# -_-.net
KiCad netlist of a schematic drawn in Altium Designer
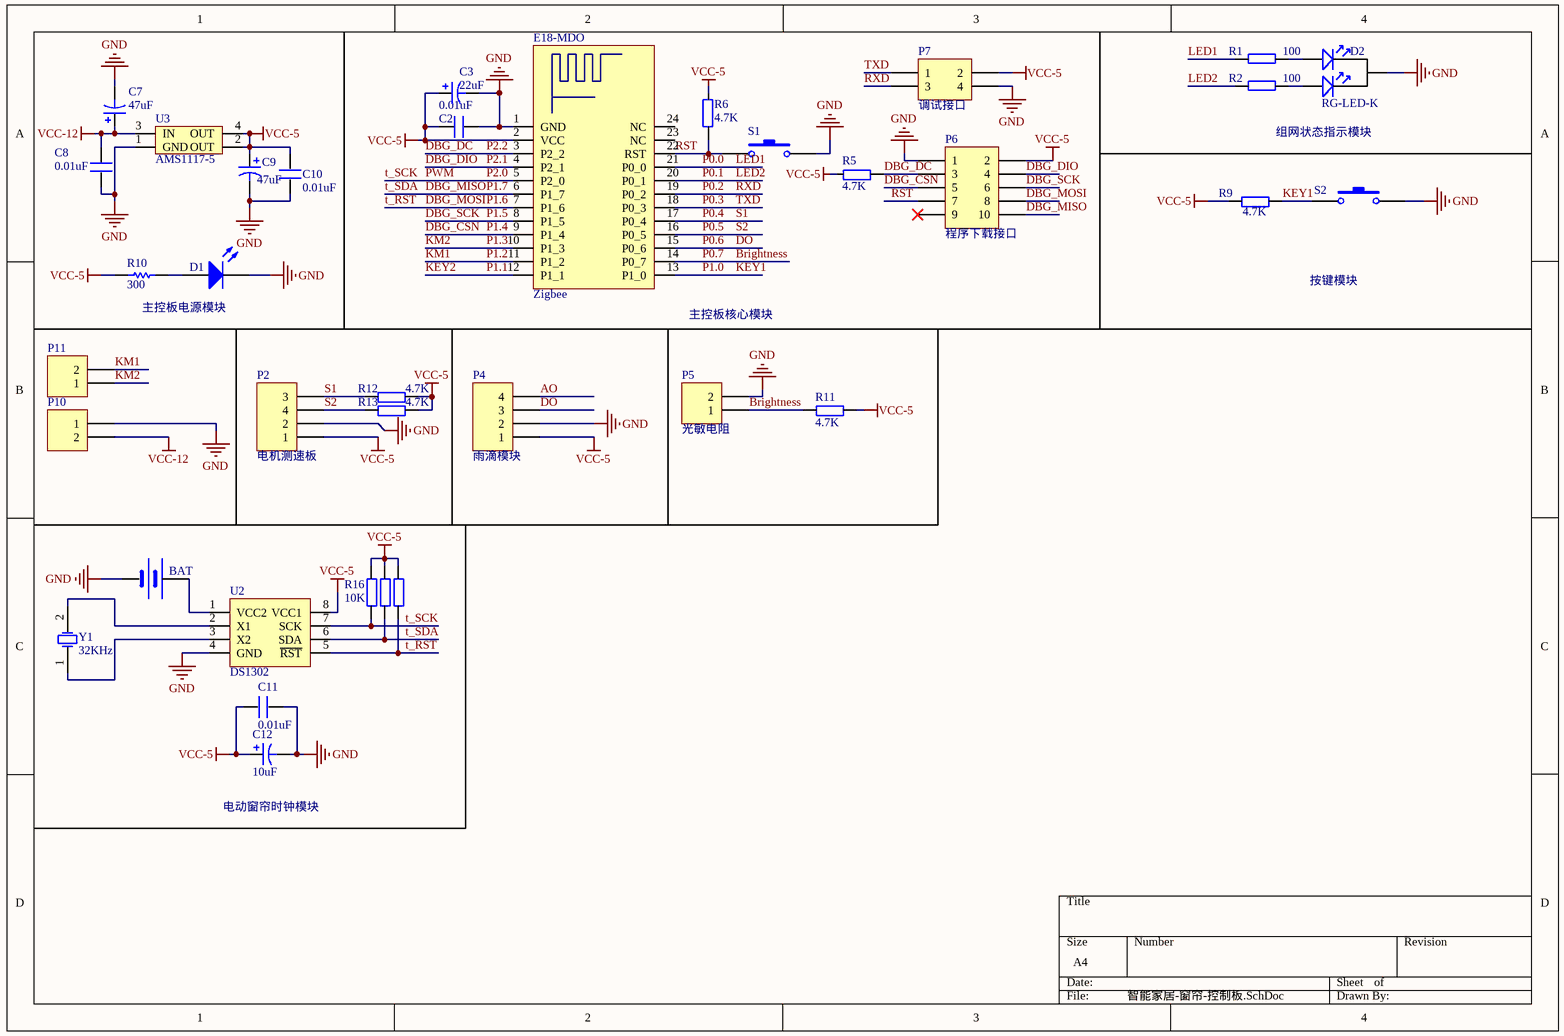
[diagram p0: 智能家居-窗帘-控制板.SchDoc]

(export (version "E")
  (design (tool "Eeschema 10.0.6"))
  (components
    (comp (ref "BAT") (value "BATT") (footprint "BATM") (libsource (lib "WARSHIP") (part "BAT")))
    (comp (ref "C2") (value "0.01uF") (footprint "0.1UF") (libsource (lib "WARSHIP") (part "C")))
    (comp (ref "C3")
      (value "22uF")
      (footprint "CD5")
      (description "Polarized Capacitor (Radial)")
      (fields (field (name "Comment") "Cap Pol1") (field (name "PUBLISHER") "Altium Limited"))
      (libsource (lib "Miscellaneous Devices") (part "Cap Pol1"))
    )
    (comp (ref "C7")
      (value "47uF")
      (footprint "CD5")
      (description "Polarized Capacitor (Radial)")
      (fields (field (name "Comment") "Cap Pol1") (field (name "PUBLISHER") "Altium Limited"))
      (libsource (lib "Miscellaneous Devices") (part "Cap Pol1"))
    )
    (comp (ref "C8") (value "0.01uF") (footprint "0.1UF") (libsource (lib "WARSHIP") (part "C")))
    (comp (ref "C9")
      (value "47uF")
      (footprint "CD5")
      (description "Polarized Capacitor (Radial)")
      (fields (field (name "Comment") "Cap Pol1") (field (name "PUBLISHER") "Altium Limited"))
      (libsource (lib "Miscellaneous Devices") (part "Cap Pol1"))
    )
    (comp (ref "C10") (value "0.01uF") (footprint "0.1UF") (libsource (lib "WARSHIP") (part "C")))
    (comp (ref "C11") (value "0.01uF") (footprint "0.1UF") (libsource (lib "WARSHIP") (part "C")))
    (comp (ref "C12")
      (value "10uF")
      (footprint "CD5")
      (description "Polarized Capacitor (Radial)")
      (fields (field (name "Comment") "Cap Pol1") (field (name "PUBLISHER") "Altium Limited"))
      (libsource (lib "Miscellaneous Devices") (part "Cap Pol1"))
    )
    (comp (ref "D1")
      (value "LED0")
      (footprint "LED-3")
      (description "Typical INFRARED GaAs LED")
      (fields (field (name "PUBLISHER") "Altium Limited"))
      (libsource (lib "Miscellaneous Devices") (part "LED0"))
    )
    (comp (ref "D2")
      (value "RG-LED-K")
      (footprint "RG-LED")
      (libsource (lib "ESP8266V1.2") (part "RG-LED-K"))
    )
    (comp (ref "E18-MDO")
      (value "Zigbee")
      (footprint "E18-MD0-1")
      (description "Zigbee模块")
      (libsource (lib "ESP8266V1.2") (part "E18-MDO"))
    )
    (comp (ref "P2")
      (value "电机测速板")
      (footprint "HDR1X4")
      (description "Header, 4-Pin")
      (fields (field (name "PUBLISHER") "Altium Limited"))
      (libsource (lib "") (part "Header 4_1"))
    )
    (comp (ref "P4")
      (value "雨滴模块")
      (footprint "DG1284")
      (description "Header, 4-Pin")
      (fields (field (name "PUBLISHER") "Altium Limited"))
      (libsource (lib "Miscellaneous Connectors") (part "Header 4"))
    )
    (comp (ref "P5")
      (value "光敏电阻")
      (footprint "HDR1X2")
      (description "Header, 2-Pin")
      (fields (field (name "PUBLISHER") "Altium Limited"))
      (libsource (lib "") (part "Header 2_1"))
    )
    (comp (ref "P6")
      (value "程序下载接口")
      (footprint "HDR2X5")
      (description "Header, 5-Pin, Dual row")
      (fields (field (name "PUBLISHER") "Altium Limited"))
      (libsource (lib "Miscellaneous Connectors") (part "Header 5X2"))
    )
    (comp (ref "P7")
      (value "调试接口")
      (footprint "HDR2X2")
      (description "Header, 2-Pin, Dual row, Right Angle")
      (fields (field (name "PUBLISHER") "Altium Limited"))
      (libsource (lib "Miscellaneous Connectors") (part "Header 2X2H"))
    )
    (comp (ref "P10")
      (value "Header 2")
      (footprint "TJC3-2A")
      (description "Header, 2-Pin")
      (fields (field (name "PUBLISHER") "Altium Limited"))
      (libsource (lib "Miscellaneous Connectors") (part "Header 2"))
    )
    (comp (ref "P11")
      (value "Header 2")
      (footprint "TJC3-2A")
      (description "Header, 2-Pin")
      (fields (field (name "PUBLISHER") "Altium Limited"))
      (libsource (lib "") (part "Header 2_1"))
    )
    (comp (ref "R1") (value "100") (footprint "AXIAL-0.3") (libsource (lib "ESP8266V1.2") (part "R")))
    (comp (ref "R2") (value "100") (footprint "AXIAL-0.3") (libsource (lib "ESP8266V1.2") (part "R")))
    (comp (ref "R5") (value "4.7K") (footprint "AXIAL-0.3") (libsource (lib "ESP8266V1.2") (part "R")))
    (comp (ref "R6") (value "4.7K") (footprint "AXIAL-0.3") (libsource (lib "ESP8266V1.2") (part "R")))
    (comp (ref "R9") (value "4.7K") (footprint "AXIAL-0.3") (libsource (lib "ESP8266V1.2") (part "R")))
    (comp (ref "R10")
      (value "300")
      (footprint "AXIAL-0.3")
      (description "Resistor")
      (fields (field (name "Comment") "Res1") (field (name "PUBLISHER") "Altium Limited"))
      (libsource (lib "Miscellaneous Devices") (part "Res1"))
    )
    (comp (ref "R11") (value "4.7K") (footprint "AXIAL-0.3") (libsource (lib "ESP8266V1.2") (part "R")))
    (comp (ref "R12") (value "4.7K") (footprint "AXIAL-0.4") (libsource (lib "ESP8266V1.2") (part "R")))
    (comp (ref "R13") (value "4.7K") (footprint "AXIAL-0.4") (libsource (lib "ESP8266V1.2") (part "R")))
    (comp (ref "R16") (value "10K") (footprint "AXIAL-0.3") (libsource (lib "ESP8266V1.2") (part "R")))
    (comp (ref "R17") (value "10K") (footprint "AXIAL-0.3") (libsource (lib "ESP8266V1.2") (part "R")))
    (comp (ref "R18") (value "10K") (footprint "AXIAL-0.3") (libsource (lib "ESP8266V1.2") (part "R")))
    (comp (ref "S1")
      (value "SW-PB")
      (footprint "KEY_M")
      (description "Switch")
      (fields (field (name "PUBLISHER") "Altium Limited"))
      (libsource (lib "Miscellaneous Devices") (part "SW-PB"))
    )
    (comp (ref "S2")
      (value "SW-PB")
      (footprint "KEY_M")
      (description "Switch")
      (fields (field (name "PUBLISHER") "Altium Limited"))
      (libsource (lib "Miscellaneous Devices") (part "SW-PB"))
    )
    (comp (ref "U2") (value "DS1302") (footprint "DIP-8N") (libsource (lib "杂项库") (part "DS1302")))
    (comp (ref "U3") (value "AMS1117-5") (footprint "AMS1117") (libsource (lib "WARSHIP") (part "AMS1117")))
    (comp (ref "Y1")
      (value "32KHz")
      (footprint "3216")
      (description "Crystal Oscillator")
      (fields (field (name "PUBLISHER") "Altium Limited"))
      (libsource (lib "Miscellaneous Devices") (part "XTAL"))
    )
  )
  (nets
    (net (code "1") (name "/AO") (class "Default")
      (node (ref "P4") (pin "4") (pinfunction "4_4") (pintype "passive"))
    )
    (net (code "2") (name "/Brightness") (class "Default")
      (node (ref "E18-MDO") (pin "14") (pinfunction "P0_7_14") (pintype "passive"))
      (node (ref "P5") (pin "1") (pinfunction "1_1") (pintype "passive"))
      (node (ref "R11") (pin "1") (pintype "passive"))
    )
    (net (code "3") (name "/DBG_CSN") (class "Default")
      (node (ref "E18-MDO") (pin "9") (pinfunction "P1_4_9") (pintype "passive"))
      (node (ref "P6") (pin "5") (pinfunction "5_5") (pintype "passive"))
    )
    (net (code "4") (name "/DBG_DC") (class "Default")
      (node (ref "E18-MDO") (pin "3") (pinfunction "P2_2_3") (pintype "passive"))
      (node (ref "P6") (pin "3") (pinfunction "3_3") (pintype "passive"))
      (node (ref "R5") (pin "2") (pintype "passive"))
    )
    (net (code "5") (name "/DBG_DIO") (class "Default")
      (node (ref "E18-MDO") (pin "4") (pinfunction "P2_1_4") (pintype "passive"))
      (node (ref "P6") (pin "4") (pinfunction "4_4") (pintype "passive"))
    )
    (net (code "6") (name "/DBG_MISO") (class "Default")
      (node (ref "E18-MDO") (pin "6") (pinfunction "P1_7_6") (pintype "passive"))
      (node (ref "P6") (pin "10") (pinfunction "10_10") (pintype "passive"))
      (node (ref "R17") (pin "1") (pintype "passive"))
      (node (ref "U2") (pin "6") (pinfunction "SDA_6") (pintype "passive"))
    )
    (net (code "7") (name "/DBG_MOSI") (class "Default")
      (node (ref "E18-MDO") (pin "7") (pinfunction "P1_6_7") (pintype "passive"))
      (node (ref "P6") (pin "8") (pinfunction "8_8") (pintype "passive"))
      (node (ref "R18") (pin "1") (pintype "passive"))
      (node (ref "U2") (pin "5") (pinfunction "~{RST}_5") (pintype "passive"))
    )
    (net (code "8") (name "/DBG_SCK") (class "Default")
      (node (ref "E18-MDO") (pin "8") (pinfunction "P1_5_8") (pintype "passive"))
      (node (ref "P6") (pin "6") (pinfunction "6_6") (pintype "passive"))
    )
    (net (code "9") (name "/DO") (class "Default")
      (node (ref "E18-MDO") (pin "15") (pinfunction "P0_6_15") (pintype "passive"))
      (node (ref "P4") (pin "3") (pinfunction "3_3") (pintype "passive"))
    )
    (net (code "10") (name "/KEY1") (class "Default")
      (node (ref "E18-MDO") (pin "13") (pinfunction "P1_0_13") (pintype "passive"))
      (node (ref "R9") (pin "2") (pintype "passive"))
      (node (ref "S2") (pin "1") (pinfunction "1_1") (pintype "passive"))
    )
    (net (code "11") (name "/KEY2") (class "Default")
      (node (ref "E18-MDO") (pin "12") (pinfunction "P1_1_12") (pintype "passive"))
    )
    (net (code "12") (name "/KM1") (class "Default")
      (node (ref "E18-MDO") (pin "11") (pinfunction "P1_2_11") (pintype "passive"))
      (node (ref "P11") (pin "2") (pinfunction "2_2") (pintype "passive"))
    )
    (net (code "13") (name "/KM2") (class "Default")
      (node (ref "E18-MDO") (pin "10") (pinfunction "P1_3_10") (pintype "passive"))
      (node (ref "P11") (pin "1") (pinfunction "1_1") (pintype "passive"))
    )
    (net (code "14") (name "/LED1") (class "Default")
      (node (ref "E18-MDO") (pin "21") (pinfunction "P0_0_21") (pintype "passive"))
      (node (ref "R1") (pin "2") (pintype "passive"))
    )
    (net (code "15") (name "/LED2") (class "Default")
      (node (ref "E18-MDO") (pin "20") (pinfunction "P0_1_20") (pintype "passive"))
      (node (ref "R2") (pin "2") (pintype "passive"))
    )
    (net (code "16") (name "/P0.2") (class "Default")
      (node (ref "E18-MDO") (pin "19") (pinfunction "P0_2_19") (pintype "passive"))
      (node (ref "P7") (pin "3") (pinfunction "3_3") (pintype "passive"))
    )
    (net (code "17") (name "/P0.3") (class "Default")
      (node (ref "E18-MDO") (pin "18") (pinfunction "P0_3_18") (pintype "passive"))
      (node (ref "P7") (pin "1") (pinfunction "1_1") (pintype "passive"))
    )
    (net (code "18") (name "/P0.4") (class "Default")
      (node (ref "E18-MDO") (pin "17") (pinfunction "P0_4_17") (pintype "passive"))
      (node (ref "P2") (pin "3") (pinfunction "3_3") (pintype "passive"))
      (node (ref "R12") (pin "1") (pintype "passive"))
    )
    (net (code "19") (name "/P0.5") (class "Default")
      (node (ref "E18-MDO") (pin "16") (pinfunction "P0_5_16") (pintype "passive"))
      (node (ref "P2") (pin "4") (pinfunction "4_4") (pintype "passive"))
      (node (ref "R13") (pin "1") (pintype "passive"))
    )
    (net (code "20") (name "/P2.0") (class "Default")
      (node (ref "E18-MDO") (pin "5") (pinfunction "P2_0_5") (pintype "passive"))
      (node (ref "R16") (pin "1") (pintype "passive"))
      (node (ref "U2") (pin "7") (pinfunction "SCK_7") (pintype "passive"))
    )
    (net (code "21") (name "/RST") (class "Default")
      (node (ref "E18-MDO") (pin "22") (pinfunction "RST_22") (pintype "passive"))
      (node (ref "P6") (pin "7") (pinfunction "7_7") (pintype "passive"))
      (node (ref "R6") (pin "2") (pintype "passive"))
      (node (ref "S1") (pin "1") (pinfunction "1_1") (pintype "passive"))
    )
    (net (code "22") (name "GND") (class "Default")
      (node (ref "BAT") (pin "2") (pinfunction "GND_2") (pintype "passive"))
      (node (ref "C10") (pin "1") (pintype "passive"))
      (node (ref "C11") (pin "2") (pintype "passive"))
      (node (ref "C12") (pin "2") (pinfunction "2_2") (pintype "passive"))
      (node (ref "C2") (pin "2") (pintype "passive"))
      (node (ref "C3") (pin "2") (pinfunction "2_2") (pintype "passive"))
      (node (ref "C7") (pin "2") (pinfunction "2_2") (pintype "passive"))
      (node (ref "C8") (pin "1") (pintype "passive"))
      (node (ref "C9") (pin "2") (pinfunction "2_2") (pintype "passive"))
      (node (ref "D1") (pin "2") (pinfunction "K_2") (pintype "passive"))
      (node (ref "D2") (pin "2") (pinfunction "GND_2") (pintype "passive"))
      (node (ref "E18-MDO") (pin "1") (pinfunction "GND_1") (pintype "passive"))
      (node (ref "P10") (pin "1") (pinfunction "1_1") (pintype "passive"))
      (node (ref "P2") (pin "2") (pinfunction "2_2") (pintype "passive"))
      (node (ref "P4") (pin "2") (pinfunction "2_2") (pintype "passive"))
      (node (ref "P5") (pin "2") (pinfunction "2_2") (pintype "passive"))
      (node (ref "P6") (pin "1") (pinfunction "1_1") (pintype "passive"))
      (node (ref "P7") (pin "4") (pinfunction "4_4") (pintype "passive"))
      (node (ref "S1") (pin "2") (pinfunction "2_2") (pintype "passive"))
      (node (ref "S2") (pin "2") (pinfunction "2_2") (pintype "passive"))
      (node (ref "U2") (pin "4") (pinfunction "GND_4") (pintype "passive"))
      (node (ref "U3") (pin "1") (pinfunction "GND_1") (pintype "passive"))
    )
    (net (code "23") (name "Net-(BAT-VCC)") (class "Default")
      (node (ref "BAT") (pin "1") (pinfunction "VCC_1") (pintype "passive"))
      (node (ref "U2") (pin "1") (pinfunction "VCC2_1") (pintype "passive"))
    )
    (net (code "24") (name "Net-(D1-A)") (class "Default")
      (node (ref "D1") (pin "1") (pinfunction "A_1") (pintype "passive"))
      (node (ref "R10") (pin "2") (pinfunction "2_2") (pintype "passive"))
    )
    (net (code "25") (name "Net-(D2-G)") (class "Default")
      (node (ref "D2") (pin "3") (pinfunction "G_3") (pintype "passive"))
      (node (ref "R2") (pin "1") (pintype "passive"))
    )
    (net (code "26") (name "Net-(D2-R)") (class "Default")
      (node (ref "D2") (pin "1") (pinfunction "R_1") (pintype "passive"))
      (node (ref "R1") (pin "1") (pintype "passive"))
    )
    (net (code "27") (name "Net-(U2-X1)") (class "Default")
      (node (ref "U2") (pin "2") (pinfunction "X1_2") (pintype "passive"))
      (node (ref "Y1") (pin "2") (pinfunction "OSC2_2") (pintype "passive"))
    )
    (net (code "28") (name "Net-(U2-X2)") (class "Default")
      (node (ref "U2") (pin "3") (pinfunction "X2_3") (pintype "passive"))
      (node (ref "Y1") (pin "1") (pinfunction "OSC1_1") (pintype "passive"))
    )
    (net (code "29") (name "VCC-5") (class "Default")
      (node (ref "C10") (pin "2") (pintype "passive"))
      (node (ref "C11") (pin "1") (pintype "passive"))
      (node (ref "C12") (pin "1") (pinfunction "1_1") (pintype "passive"))
      (node (ref "C2") (pin "1") (pintype "passive"))
      (node (ref "C3") (pin "1") (pinfunction "1_1") (pintype "passive"))
      (node (ref "C9") (pin "1") (pinfunction "1_1") (pintype "passive"))
      (node (ref "E18-MDO") (pin "2") (pinfunction "VCC_2") (pintype "passive"))
      (node (ref "P2") (pin "1") (pinfunction "1_1") (pintype "passive"))
      (node (ref "P4") (pin "1") (pinfunction "1_1") (pintype "passive"))
      (node (ref "P6") (pin "2") (pinfunction "2_2") (pintype "passive"))
      (node (ref "P7") (pin "2") (pinfunction "2_2") (pintype "passive"))
      (node (ref "R10") (pin "1") (pinfunction "1_1") (pintype "passive"))
      (node (ref "R11") (pin "2") (pintype "passive"))
      (node (ref "R12") (pin "2") (pintype "passive"))
      (node (ref "R13") (pin "2") (pintype "passive"))
      (node (ref "R16") (pin "2") (pintype "passive"))
      (node (ref "R17") (pin "2") (pintype "passive"))
      (node (ref "R18") (pin "2") (pintype "passive"))
      (node (ref "R5") (pin "1") (pintype "passive"))
      (node (ref "R6") (pin "1") (pintype "passive"))
      (node (ref "R9") (pin "1") (pintype "passive"))
      (node (ref "U2") (pin "8") (pinfunction "VCC1_8") (pintype "passive"))
      (node (ref "U3") (pin "2") (pinfunction "OUT_2") (pintype "passive"))
      (node (ref "U3") (pin "4") (pinfunction "OUT_4") (pintype "passive"))
    )
    (net (code "30") (name "VCC-12") (class "Default")
      (node (ref "C7") (pin "1") (pinfunction "1_1") (pintype "passive"))
      (node (ref "C8") (pin "2") (pintype "passive"))
      (node (ref "P10") (pin "2") (pinfunction "2_2") (pintype "passive"))
      (node (ref "U3") (pin "3") (pinfunction "IN_3") (pintype "passive"))
    )
    (net (code "31") (name "unconnected-(E18-MDO-NC-Pad23)") (class "Default")
      (node (ref "E18-MDO") (pin "23") (pinfunction "NC_23") (pintype "passive"))
    )
    (net (code "32") (name "unconnected-(E18-MDO-NC-Pad24)") (class "Default")
      (node (ref "E18-MDO") (pin "24") (pinfunction "NC_24") (pintype "passive"))
    )
    (net (code "33") (name "unconnected-(P6-Pad9)") (class "Default")
      (node (ref "P6") (pin "9") (pinfunction "9_9") (pintype "passive+no_connect"))
    )
  )
)
